# chipset.net
KiCad netlist of a schematic drawn in EAGLE
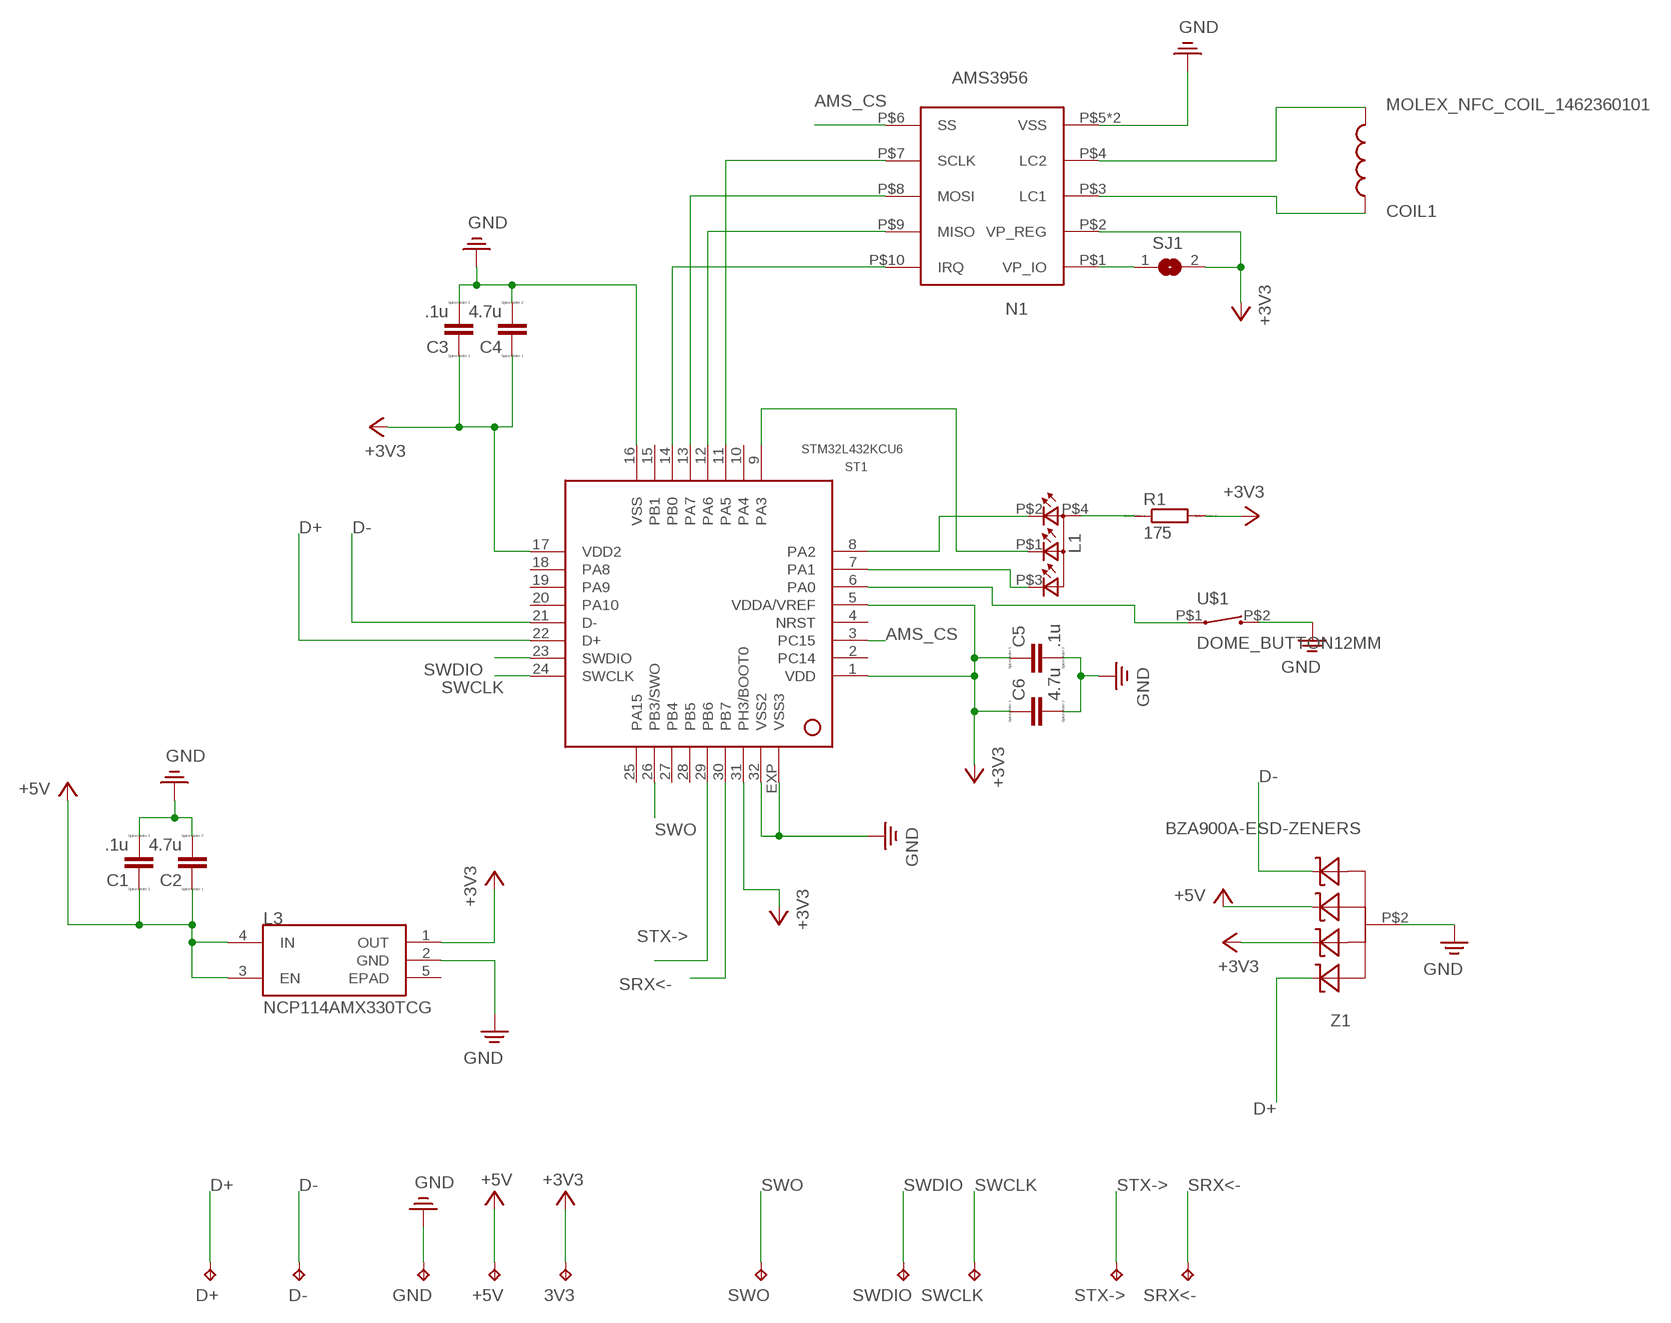
[diagram p0: schematic, sheet 1]

(export (version "E")
  (design (tool "Eeschema 10.0.6"))
  (components
    (comp (ref "+5V")
      (value "TEST_POINT")
      (footprint "eagle-import:B1,27")
      (libsource (lib "eagle-import") (part "TEST_POINT"))
    )
    (comp (ref "3V3")
      (value "TEST_POINT")
      (footprint "eagle-import:B1,27")
      (libsource (lib "eagle-import") (part "TEST_POINT"))
    )
    (comp (ref "C1")
      (value ".1u")
      (footprint "eagle-import:C0402")
      (libsource (lib "eagle-import") (part "CAPACITOR"))
    )
    (comp (ref "C2")
      (value "4.7u")
      (footprint "eagle-import:C0402")
      (libsource (lib "eagle-import") (part "CAPACITOR"))
    )
    (comp (ref "C3")
      (value ".1u")
      (footprint "eagle-import:C0402")
      (libsource (lib "eagle-import") (part "CAPACITOR"))
    )
    (comp (ref "C4")
      (value "4.7u")
      (footprint "eagle-import:C0402")
      (libsource (lib "eagle-import") (part "CAPACITOR"))
    )
    (comp (ref "C5")
      (value ".1u")
      (footprint "eagle-import:C0402")
      (libsource (lib "eagle-import") (part "CAPACITOR"))
    )
    (comp (ref "C6")
      (value "4.7u")
      (footprint "eagle-import:C0402")
      (libsource (lib "eagle-import") (part "CAPACITOR"))
    )
    (comp (ref "COIL1")
      (value "MOLEX_NFC_COIL_1462360101")
      (footprint "eagle-import:MOLEX_NFC_COIL1")
      (fields (field (name "MPN") "1462360101"))
      (libsource (lib "eagle-import") (part "MOLEX_NFC_COIL_1462360101"))
    )
    (comp (ref "D+")
      (value "TEST_POINT")
      (footprint "eagle-import:B1,27")
      (libsource (lib "eagle-import") (part "TEST_POINT"))
    )
    (comp (ref "D-")
      (value "TEST_POINT")
      (footprint "eagle-import:B1,27")
      (libsource (lib "eagle-import") (part "TEST_POINT"))
    )
    (comp (ref "GND")
      (value "TEST_POINT")
      (footprint "eagle-import:B1,27")
      (libsource (lib "eagle-import") (part "TEST_POINT"))
    )
    (comp (ref "L1")
      (value "EAST1616RGBA3-LED-RGBCL-505S-X-SD-T")
      (footprint "eagle-import:CL-505S-X-SD-T")
      (libsource (lib "eagle-import") (part "EAST1616RGBA3-LED-RGBCL-505S-X-SD-T"))
    )
    (comp (ref "L3")
      (value "NCP114AMX330TCG")
      (footprint "eagle-import:REG_NCP114AMX330TCG")
      (fields (field (name "MF") "ON Semiconductor"))
      (libsource (lib "eagle-import") (part "NCP114AMX330TCG"))
    )
    (comp (ref "N1")
      (value "AMS3956")
      (footprint "eagle-import:MLPD3X3")
      (libsource (lib "eagle-import") (part "AMS3956"))
    )
    (comp (ref "R1")
      (value "175")
      (footprint "eagle-import:R0402")
      (libsource (lib "eagle-import") (part "RESISTOR"))
    )
    (comp (ref "SJ1") (value "SJ") (footprint "eagle-import:SJ") (libsource (lib "eagle-import") (part "SJ")))
    (comp (ref "SRX<-")
      (value "TEST_POINT")
      (footprint "eagle-import:B1,27")
      (libsource (lib "eagle-import") (part "TEST_POINT"))
    )
    (comp (ref "ST1")
      (value "STM32L432KCU6")
      (footprint "eagle-import:QFN32")
      (libsource (lib "eagle-import") (part "STM32L432KCU6"))
    )
    (comp (ref "STX->")
      (value "TEST_POINT")
      (footprint "eagle-import:B1,27")
      (libsource (lib "eagle-import") (part "TEST_POINT"))
    )
    (comp (ref "SWCLK")
      (value "TEST_POINT")
      (footprint "eagle-import:B1,27")
      (libsource (lib "eagle-import") (part "TEST_POINT"))
    )
    (comp (ref "SWDIO")
      (value "TEST_POINT")
      (footprint "eagle-import:B1,27")
      (libsource (lib "eagle-import") (part "TEST_POINT"))
    )
    (comp (ref "SWO")
      (value "TEST_POINT")
      (footprint "eagle-import:B1,27")
      (libsource (lib "eagle-import") (part "TEST_POINT"))
    )
    (comp (ref "U$1")
      (value "DOME_BUTTON12MM")
      (footprint "eagle-import:DOME-BL-12MM")
      (libsource (lib "eagle-import") (part "DOME_BUTTON12MM"))
    )
    (comp (ref "Z1")
      (value "BZA900A-ESD-ZENERS")
      (footprint "eagle-import:BZA900A")
      (libsource (lib "eagle-import") (part "BZA900A-ESD-ZENERS"))
    )
  )
  (nets
    (net (code "1") (name "+3V3") (class "Default")
      (node (ref "3V3") (pin "TP") (pinfunction "TP_TP") (pintype "input"))
      (node (ref "C3") (pin "1") (pinfunction "1_1") (pintype "passive"))
      (node (ref "C4") (pin "1") (pinfunction "1_1") (pintype "passive"))
      (node (ref "C5") (pin "1") (pinfunction "1_1") (pintype "passive"))
      (node (ref "C6") (pin "1") (pinfunction "1_1") (pintype "passive"))
      (node (ref "L3") (pin "1") (pinfunction "OUT_1") (pintype "output"))
      (node (ref "N1") (pin "P$2") (pinfunction "VP_REG_P$2") (pintype "bidirectional"))
      (node (ref "R1") (pin "2") (pinfunction "2_2") (pintype "passive"))
      (node (ref "SJ1") (pin "2") (pinfunction "2_2") (pintype "passive"))
      (node (ref "ST1") (pin "1") (pinfunction "VDD_1") (pintype "bidirectional"))
      (node (ref "ST1") (pin "17") (pinfunction "VDD2_17") (pintype "bidirectional"))
      (node (ref "ST1") (pin "31") (pinfunction "PH3/BOOT0_31") (pintype "bidirectional"))
      (node (ref "ST1") (pin "5") (pinfunction "VDDA/VREF_5") (pintype "bidirectional"))
      (node (ref "Z1") (pin "P$5") (pinfunction "C1_P$5") (pintype "passive"))
    )
    (net (code "2") (name "+5V") (class "Default")
      (node (ref "+5V") (pin "TP") (pinfunction "TP_TP") (pintype "input"))
      (node (ref "C1") (pin "1") (pinfunction "1_1") (pintype "passive"))
      (node (ref "C2") (pin "1") (pinfunction "1_1") (pintype "passive"))
      (node (ref "L3") (pin "3") (pinfunction "EN_3") (pintype "input"))
      (node (ref "L3") (pin "4") (pinfunction "IN_4") (pintype "input"))
      (node (ref "Z1") (pin "P$1") (pinfunction "C_P$1") (pintype "passive"))
    )
    (net (code "3") (name "/AMS_CS") (class "Default")
      (node (ref "N1") (pin "P$6") (pinfunction "SS_P$6") (pintype "bidirectional"))
      (node (ref "ST1") (pin "3") (pinfunction "PC15_3") (pintype "bidirectional"))
    )
    (net (code "4") (name "/D+") (class "Default")
      (node (ref "D+") (pin "TP") (pinfunction "TP_TP") (pintype "input"))
      (node (ref "ST1") (pin "22") (pinfunction "D+_22") (pintype "bidirectional"))
      (node (ref "Z1") (pin "P$3") (pinfunction "C3_P$3") (pintype "passive"))
    )
    (net (code "5") (name "/D-") (class "Default")
      (node (ref "D-") (pin "TP") (pinfunction "TP_TP") (pintype "input"))
      (node (ref "ST1") (pin "21") (pinfunction "D-_21") (pintype "bidirectional"))
      (node (ref "Z1") (pin "P$4") (pinfunction "C2_P$4") (pintype "passive"))
    )
    (net (code "6") (name "/SRX<-") (class "Default")
      (node (ref "SRX<-") (pin "TP") (pinfunction "TP_TP") (pintype "input"))
      (node (ref "ST1") (pin "30") (pinfunction "PB7_30") (pintype "bidirectional"))
    )
    (net (code "7") (name "/STX->") (class "Default")
      (node (ref "ST1") (pin "29") (pinfunction "PB6_29") (pintype "bidirectional"))
      (node (ref "STX->") (pin "TP") (pinfunction "TP_TP") (pintype "input"))
    )
    (net (code "8") (name "/SWCLK") (class "Default")
      (node (ref "ST1") (pin "24") (pinfunction "SWCLK_24") (pintype "bidirectional"))
      (node (ref "SWCLK") (pin "TP") (pinfunction "TP_TP") (pintype "input"))
    )
    (net (code "9") (name "/SWDIO") (class "Default")
      (node (ref "ST1") (pin "23") (pinfunction "SWDIO_23") (pintype "bidirectional"))
      (node (ref "SWDIO") (pin "TP") (pinfunction "TP_TP") (pintype "input"))
    )
    (net (code "10") (name "/SWO") (class "Default")
      (node (ref "ST1") (pin "26") (pinfunction "PB3/SWO_26") (pintype "bidirectional"))
      (node (ref "SWO") (pin "TP") (pinfunction "TP_TP") (pintype "input"))
    )
    (net (code "11") (name "GND") (class "Default")
      (node (ref "C1") (pin "2") (pinfunction "2_2") (pintype "passive"))
      (node (ref "C2") (pin "2") (pinfunction "2_2") (pintype "passive"))
      (node (ref "C3") (pin "2") (pinfunction "2_2") (pintype "passive"))
      (node (ref "C4") (pin "2") (pinfunction "2_2") (pintype "passive"))
      (node (ref "C5") (pin "2") (pinfunction "2_2") (pintype "passive"))
      (node (ref "C6") (pin "2") (pinfunction "2_2") (pintype "passive"))
      (node (ref "GND") (pin "TP") (pinfunction "TP_TP") (pintype "input"))
      (node (ref "L3") (pin "2") (pinfunction "GND_2") (pintype "power_in"))
      (node (ref "N1") (pin "P$11") (pinfunction "VSS_P$11") (pintype "bidirectional"))
      (node (ref "N1") (pin "P$5") (pinfunction "VSS_P$5") (pintype "bidirectional"))
      (node (ref "ST1") (pin "16") (pinfunction "VSS_16") (pintype "bidirectional"))
      (node (ref "ST1") (pin "32") (pinfunction "VSS2_32") (pintype "bidirectional"))
      (node (ref "ST1") (pin "EXP") (pinfunction "VSS3_EXP") (pintype "bidirectional"))
      (node (ref "U$1") (pin "P$2") (pinfunction "2_P$2") (pintype "passive"))
      (node (ref "Z1") (pin "P$2") (pinfunction "P$1_P$2") (pintype "bidirectional"))
    )
    (net (code "12") (name "Net-(COIL1-1)") (class "Default")
      (node (ref "COIL1") (pin "P$1") (pinfunction "1_P$1") (pintype "passive"))
      (node (ref "N1") (pin "P$3") (pinfunction "LC1_P$3") (pintype "bidirectional"))
    )
    (net (code "13") (name "Net-(COIL1-2)") (class "Default")
      (node (ref "COIL1") (pin "P$2") (pinfunction "2_P$2") (pintype "passive"))
      (node (ref "N1") (pin "P$4") (pinfunction "LC2_P$4") (pintype "bidirectional"))
    )
    (net (code "14") (name "Net-(L1-A2)") (class "Default")
      (node (ref "L1") (pin "P$4") (pinfunction "A2_P$4") (pintype "passive"))
      (node (ref "R1") (pin "1") (pinfunction "1_1") (pintype "passive"))
    )
    (net (code "15") (name "Net-(L1-CBLUE)") (class "Default")
      (node (ref "L1") (pin "P$1") (pinfunction "CBLUE_P$1") (pintype "passive"))
      (node (ref "ST1") (pin "9") (pinfunction "PA3_9") (pintype "bidirectional"))
    )
    (net (code "16") (name "Net-(L1-CGREEN)") (class "Default")
      (node (ref "L1") (pin "P$3") (pinfunction "CGREEN_P$3") (pintype "passive"))
      (node (ref "ST1") (pin "7") (pinfunction "PA1_7") (pintype "bidirectional"))
    )
    (net (code "17") (name "Net-(L1-CRED)") (class "Default")
      (node (ref "L1") (pin "P$2") (pinfunction "CRED_P$2") (pintype "passive"))
      (node (ref "ST1") (pin "8") (pinfunction "PA2_8") (pintype "bidirectional"))
    )
    (net (code "18") (name "Net-(N1-IRQ)") (class "Default")
      (node (ref "N1") (pin "P$10") (pinfunction "IRQ_P$10") (pintype "bidirectional"))
      (node (ref "ST1") (pin "14") (pinfunction "PB0_14") (pintype "bidirectional"))
    )
    (net (code "19") (name "Net-(N1-MISO)") (class "Default")
      (node (ref "N1") (pin "P$9") (pinfunction "MISO_P$9") (pintype "bidirectional"))
      (node (ref "ST1") (pin "12") (pinfunction "PA6_12") (pintype "bidirectional"))
    )
    (net (code "20") (name "Net-(N1-MOSI)") (class "Default")
      (node (ref "N1") (pin "P$8") (pinfunction "MOSI_P$8") (pintype "bidirectional"))
      (node (ref "ST1") (pin "13") (pinfunction "PA7_13") (pintype "bidirectional"))
    )
    (net (code "21") (name "Net-(N1-SCLK)") (class "Default")
      (node (ref "N1") (pin "P$7") (pinfunction "SCLK_P$7") (pintype "bidirectional"))
      (node (ref "ST1") (pin "11") (pinfunction "PA5_11") (pintype "bidirectional"))
    )
    (net (code "22") (name "Net-(N1-VP_IO)") (class "Default")
      (node (ref "N1") (pin "P$1") (pinfunction "VP_IO_P$1") (pintype "bidirectional"))
      (node (ref "SJ1") (pin "1") (pinfunction "1_1") (pintype "passive"))
    )
    (net (code "23") (name "Net-(ST1-PA0)") (class "Default")
      (node (ref "ST1") (pin "6") (pinfunction "PA0_6") (pintype "bidirectional"))
      (node (ref "U$1") (pin "P$1") (pinfunction "1_P$1") (pintype "passive"))
    )
    (net (code "24") (name "unconnected-(L3-EPAD-Pad5)") (class "Default")
      (node (ref "L3") (pin "5") (pinfunction "EPAD_5") (pintype "passive"))
    )
    (net (code "25") (name "unconnected-(ST1-NRST-Pad4)") (class "Default")
      (node (ref "ST1") (pin "4") (pinfunction "NRST_4") (pintype "bidirectional"))
    )
    (net (code "26") (name "unconnected-(ST1-PA4-Pad10)") (class "Default")
      (node (ref "ST1") (pin "10") (pinfunction "PA4_10") (pintype "bidirectional"))
    )
    (net (code "27") (name "unconnected-(ST1-PA8-Pad18)") (class "Default")
      (node (ref "ST1") (pin "18") (pinfunction "PA8_18") (pintype "bidirectional"))
    )
    (net (code "28") (name "unconnected-(ST1-PA9-Pad19)") (class "Default")
      (node (ref "ST1") (pin "19") (pinfunction "PA9_19") (pintype "bidirectional"))
    )
    (net (code "29") (name "unconnected-(ST1-PA10-Pad20)") (class "Default")
      (node (ref "ST1") (pin "20") (pinfunction "PA10_20") (pintype "bidirectional"))
    )
    (net (code "30") (name "unconnected-(ST1-PA15-Pad25)") (class "Default")
      (node (ref "ST1") (pin "25") (pinfunction "PA15_25") (pintype "bidirectional"))
    )
    (net (code "31") (name "unconnected-(ST1-PB1-Pad15)") (class "Default")
      (node (ref "ST1") (pin "15") (pinfunction "PB1_15") (pintype "bidirectional"))
    )
    (net (code "32") (name "unconnected-(ST1-PB4-Pad27)") (class "Default")
      (node (ref "ST1") (pin "27") (pinfunction "PB4_27") (pintype "bidirectional"))
    )
    (net (code "33") (name "unconnected-(ST1-PB5-Pad28)") (class "Default")
      (node (ref "ST1") (pin "28") (pinfunction "PB5_28") (pintype "bidirectional"))
    )
    (net (code "34") (name "unconnected-(ST1-PC14-Pad2)") (class "Default")
      (node (ref "ST1") (pin "2") (pinfunction "PC14_2") (pintype "bidirectional"))
    )
  )
)
